# flyingpi.net
KiCad netlist of a schematic drawn in Altium Designer
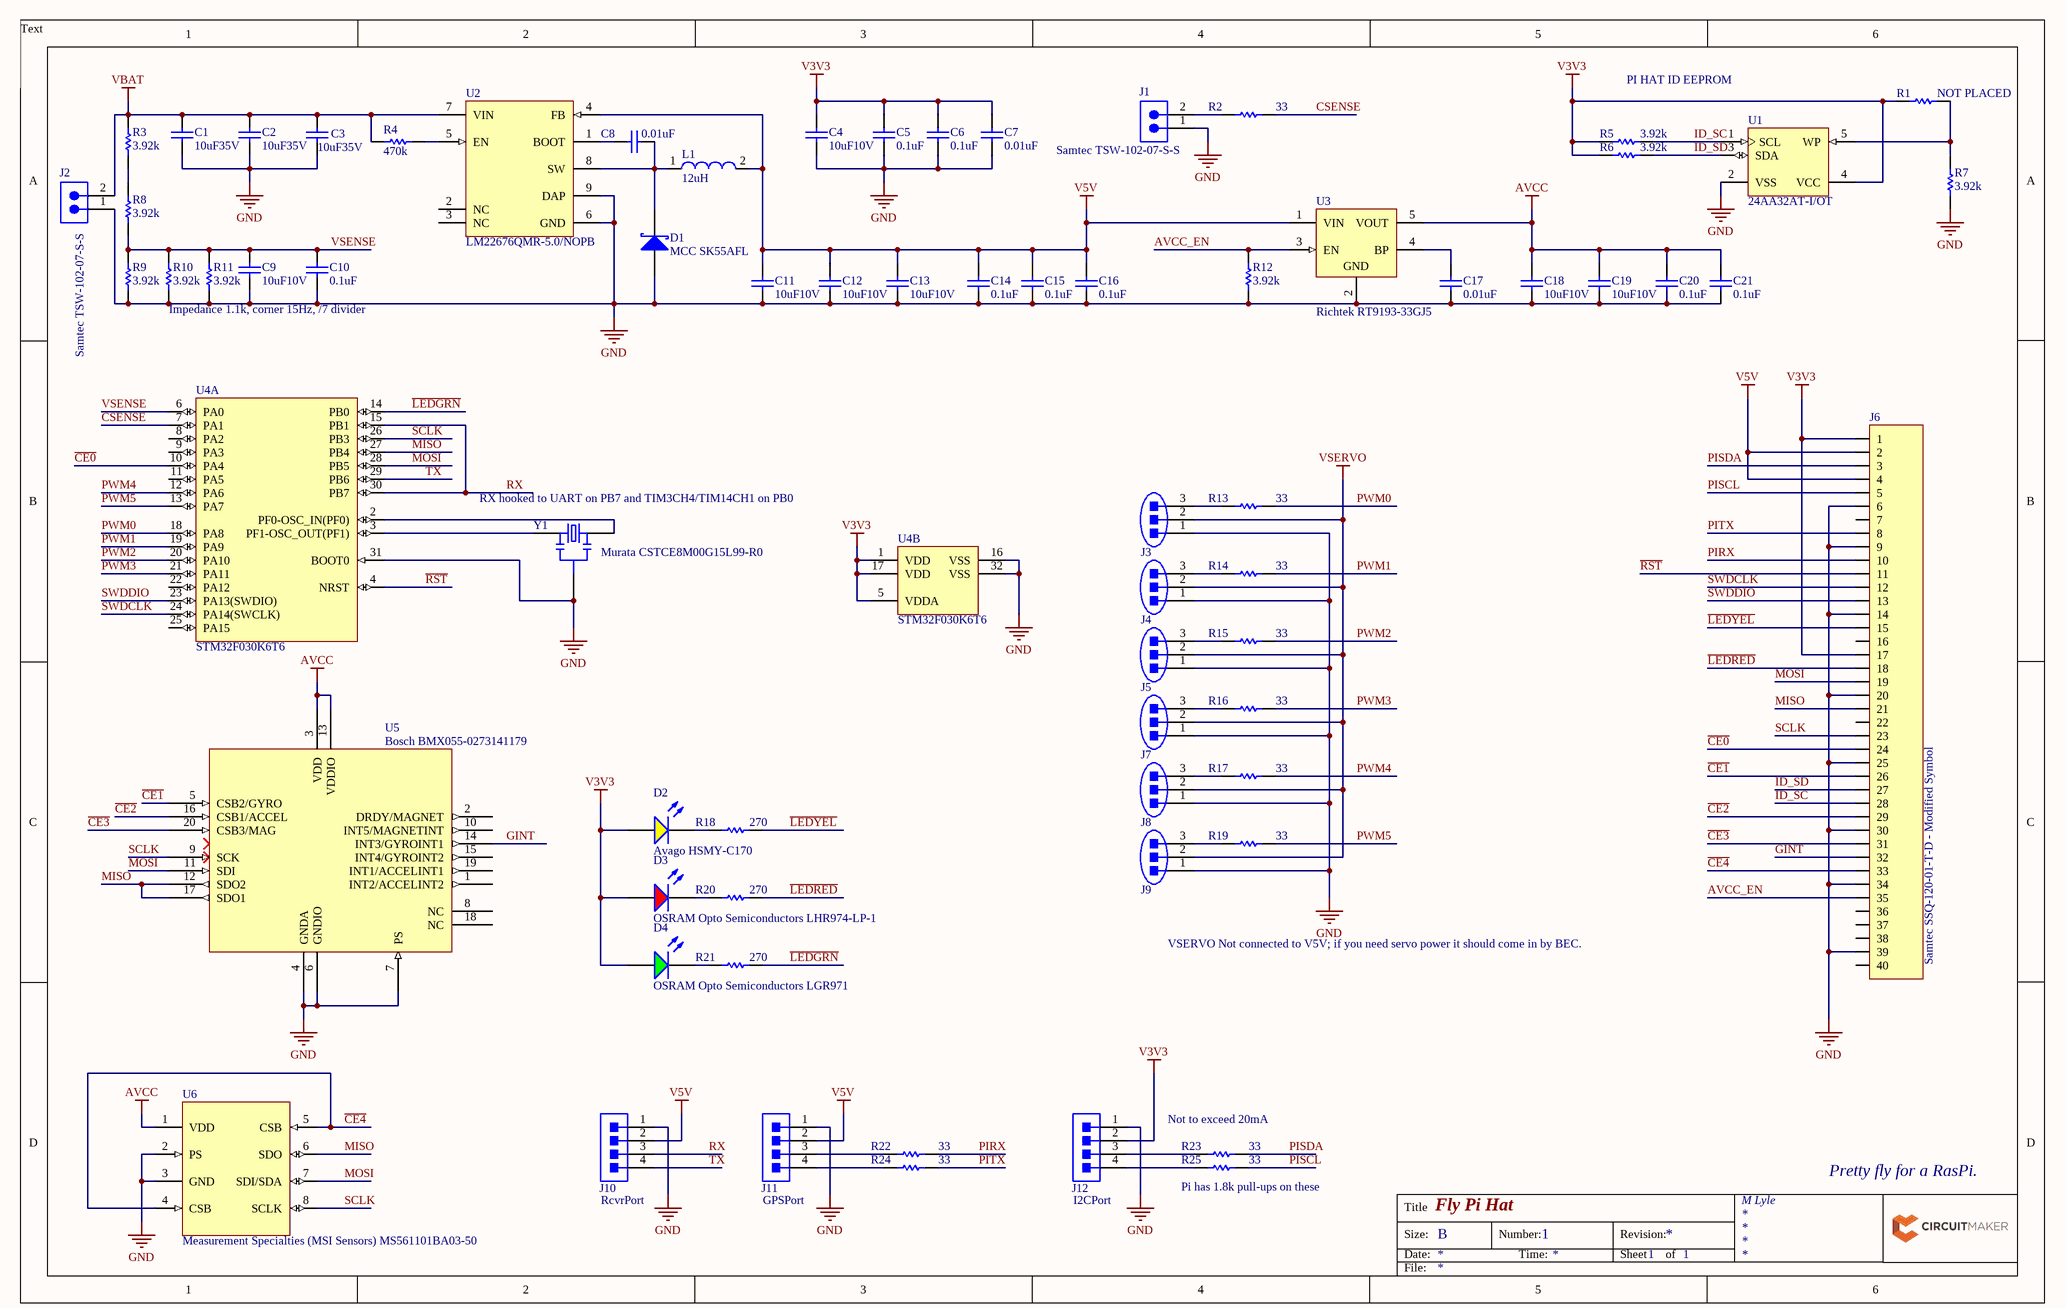
[diagram p0: flyingpi.SchDoc]

(export (version "E")
  (design (tool "Eeschema 10.0.6"))
  (components
    (comp (ref "C1")
      (value "10uF35V")
      (footprint "PCB-4097432-1")
      (description "CAP CER 10UF 35V 10% X5R 0805")
      (libsource (lib "Octopart library") (part "SYM-8857307-2"))
    )
    (comp (ref "C2")
      (value "10uF35V")
      (footprint "PCB-4097432-1")
      (description "CAP CER 10UF 35V 10% X5R 0805")
      (libsource (lib "Octopart library") (part "SYM-8857307-2"))
    )
    (comp (ref "C3")
      (value "10uF35V")
      (footprint "PCB-4097432-1")
      (description "CAP CER 10UF 35V 10% X5R 0805")
      (libsource (lib "Octopart library") (part "SYM-8857307-2"))
    )
    (comp (ref "C4")
      (value "10uF10V")
      (footprint "PCB-11286000-1")
      (description "Cap Ceramic 10uF 10V X5R 10% SMD 0603 85C Paper T/R")
      (libsource (lib "Octopart library") (part "SYM-11286000-1"))
    )
    (comp (ref "C5")
      (value "0.1uF")
      (footprint "CAPC1608X90X35LL10T15")
      (description "CAP CER 0.1UF 16V 10% X7R 0603")
      (libsource (lib "CommunityVault") (part "CAP-2"))
    )
    (comp (ref "C6")
      (value "0.1uF")
      (footprint "CAPC1608X90X35LL10T15")
      (description "CAP CER 0.1UF 16V 10% X7R 0603")
      (libsource (lib "CommunityVault") (part "CAP-2"))
    )
    (comp (ref "C7")
      (value "0.01uF")
      (footprint "0603C")
      (description "0603 10nF 50V ±10 % Tolerance X7R SMT Multilayer Ceramic Capacitor")
      (fields (field (name "MANUFACTURER PART NUMBER") "GRM188R71H103KA01D"))
      (libsource (lib "Octopart library") (part "CAP-NP-2"))
    )
    (comp (ref "C8")
      (value "0.01uF")
      (footprint "0603C")
      (description "0603 10nF 50V ±10 % Tolerance X7R SMT Multilayer Ceramic Capacitor")
      (fields (field (name "MANUFACTURER PART NUMBER") "GRM188R71H103KA01D"))
      (libsource (lib "Octopart library") (part "CAP-NP-2"))
    )
    (comp (ref "C9")
      (value "10uF10V")
      (footprint "PCB-11286000-1")
      (description "Cap Ceramic 10uF 10V X5R 10% SMD 0603 85C Paper T/R")
      (libsource (lib "Octopart library") (part "SYM-11286000-1"))
    )
    (comp (ref "C10")
      (value "0.1uF")
      (footprint "CAPC1608X90X35LL10T15")
      (description "CAP CER 0.1UF 16V 10% X7R 0603")
      (libsource (lib "CommunityVault") (part "CAP-2"))
    )
    (comp (ref "C11")
      (value "10uF10V")
      (footprint "PCB-11286000-1")
      (description "Cap Ceramic 10uF 10V X5R 10% SMD 0603 85C Paper T/R")
      (libsource (lib "Octopart library") (part "SYM-11286000-1"))
    )
    (comp (ref "C12")
      (value "10uF10V")
      (footprint "PCB-11286000-1")
      (description "Cap Ceramic 10uF 10V X5R 10% SMD 0603 85C Paper T/R")
      (libsource (lib "Octopart library") (part "SYM-11286000-1"))
    )
    (comp (ref "C13")
      (value "10uF10V")
      (footprint "PCB-11286000-1")
      (description "Cap Ceramic 10uF 10V X5R 10% SMD 0603 85C Paper T/R")
      (libsource (lib "Octopart library") (part "SYM-11286000-1"))
    )
    (comp (ref "C14")
      (value "0.1uF")
      (footprint "CAPC1608X90X35LL10T15")
      (description "CAP CER 0.1UF 16V 10% X7R 0603")
      (libsource (lib "CommunityVault") (part "CAP-2"))
    )
    (comp (ref "C15")
      (value "0.1uF")
      (footprint "CAPC1608X90X35LL10T15")
      (description "CAP CER 0.1UF 16V 10% X7R 0603")
      (libsource (lib "CommunityVault") (part "CAP-2"))
    )
    (comp (ref "C16")
      (value "0.1uF")
      (footprint "CAPC1608X90X35LL10T15")
      (description "CAP CER 0.1UF 16V 10% X7R 0603")
      (libsource (lib "CommunityVault") (part "CAP-2"))
    )
    (comp (ref "C17")
      (value "0.01uF")
      (footprint "0603C")
      (description "0603 10nF 50V ±10 % Tolerance X7R SMT Multilayer Ceramic Capacitor")
      (fields (field (name "MANUFACTURER PART NUMBER") "GRM188R71H103KA01D"))
      (libsource (lib "Octopart library") (part "CAP-NP-2"))
    )
    (comp (ref "C18")
      (value "10uF10V")
      (footprint "PCB-11286000-1")
      (description "Cap Ceramic 10uF 10V X5R 10% SMD 0603 85C Paper T/R")
      (libsource (lib "Octopart library") (part "SYM-11286000-1"))
    )
    (comp (ref "C19")
      (value "10uF10V")
      (footprint "PCB-11286000-1")
      (description "Cap Ceramic 10uF 10V X5R 10% SMD 0603 85C Paper T/R")
      (libsource (lib "Octopart library") (part "SYM-11286000-1"))
    )
    (comp (ref "C20")
      (value "0.1uF")
      (footprint "CAPC1608X90X35LL10T15")
      (description "CAP CER 0.1UF 16V 10% X7R 0603")
      (libsource (lib "CommunityVault") (part "CAP-2"))
    )
    (comp (ref "C21")
      (value "0.1uF")
      (footprint "CAPC1608X90X35LL10T15")
      (description "CAP CER 0.1UF 16V 10% X7R 0603")
      (libsource (lib "CommunityVault") (part "CAP-2"))
    )
    (comp (ref "D1")
      (value "MCC SK55AFL")
      (footprint "SODFL500X120-2N")
      (description "Diode Schottky 50v 5a Do221ac")
      (fields (field (name "MANUFACTURER PART NUMBER") "SK55AFL-TP"))
      (libsource (lib "Octopart library") (part "SYM-87164cce30a458d1-1"))
    )
    (comp (ref "D2")
      (value "Avago HSMY-C170")
      (footprint "SMD_LED0805")
      (description "LED 589NM YELLOW DIFF 0805 SMD")
      (libsource (lib "Octopart library") (part "LED-YELLOW-C1A2-2"))
    )
    (comp (ref "D3")
      (value "OSRAM Opto Semiconductors LHR974-LP-1")
      (footprint "LED0805")
      (description "LED CHIPLED 645NM RED DIFF 0805")
      (libsource (lib "CommunityVault") (part "LED_RED-C1A2-2"))
    )
    (comp (ref "D4")
      (value "OSRAM Opto Semiconductors LGR971")
      (footprint "LED0805")
      (description "Osram Opto CHIPLED 0805 Series 0805 Green LED, 160")
      (libsource (lib "CommunityVault") (part "LED_GREEN_C1A2-2"))
    )
    (comp (ref "J1")
      (value "Samtec TSW-102-07-S-S")
      (footprint "HDR102")
      (description "CONN HEADER 2POS .100\" SGL GOLD")
      (libsource (lib "CommunityVault") (part "Header_2x1"))
    )
    (comp (ref "J2")
      (value "Samtec TSW-102-07-S-S")
      (footprint "HDR102")
      (description "CONN HEADER 2POS .100\" SGL GOLD")
      (libsource (lib "CommunityVault") (part "Header_2x1"))
    )
    (comp (ref "J3")
      (value "TE Connectivity (Tyco Electronics) 5-146280-3")
      (footprint "HDR1x3_100mil")
      (description "CONN HEADR BRKWAY .100 3POS STR")
      (libsource (lib "CommunityVault") (part "SYM-663837-1"))
    )
    (comp (ref "J4")
      (value "TE Connectivity (Tyco Electronics) 5-146280-3")
      (footprint "HDR1x3_100mil")
      (description "CONN HEADR BRKWAY .100 3POS STR")
      (libsource (lib "CommunityVault") (part "SYM-663837-1"))
    )
    (comp (ref "J5")
      (value "TE Connectivity (Tyco Electronics) 5-146280-3")
      (footprint "HDR1x3_100mil")
      (description "CONN HEADR BRKWAY .100 3POS STR")
      (libsource (lib "CommunityVault") (part "SYM-663837-1"))
    )
    (comp (ref "J6")
      (value "Samtec SSQ-120-01-T-D - Modified Symbol")
      (footprint "PCB-677180-1")
      (description "CONN RCPT .100\" 40POS DUAL TIN")
      (libsource (lib "CommunityVault") (part "SYM-677180-1"))
    )
    (comp (ref "J7")
      (value "TE Connectivity (Tyco Electronics) 5-146280-3")
      (footprint "HDR1x3_100mil")
      (description "CONN HEADR BRKWAY .100 3POS STR")
      (libsource (lib "CommunityVault") (part "SYM-663837-1"))
    )
    (comp (ref "J8")
      (value "TE Connectivity (Tyco Electronics) 5-146280-3")
      (footprint "HDR1x3_100mil")
      (description "CONN HEADR BRKWAY .100 3POS STR")
      (libsource (lib "CommunityVault") (part "SYM-663837-1"))
    )
    (comp (ref "J9")
      (value "TE Connectivity (Tyco Electronics) 5-146280-3")
      (footprint "HDR1x3_100mil")
      (description "CONN HEADR BRKWAY .100 3POS STR")
      (libsource (lib "CommunityVault") (part "SYM-663837-1"))
    )
    (comp (ref "J10")
      (value "TE Connectivity (Tyco Electronics) 3-644456-4")
      (footprint "PCB-640283-1")
      (description "CONN HEADER VERT 4POS .100 TIN")
      (libsource (lib "CommunityVault") (part "SYM-640283-1"))
    )
    (comp (ref "J11")
      (value "TE Connectivity (Tyco Electronics) 3-644456-4")
      (footprint "PCB-640283-1")
      (description "CONN HEADER VERT 4POS .100 TIN")
      (libsource (lib "CommunityVault") (part "SYM-640283-1"))
    )
    (comp (ref "J12")
      (value "TE Connectivity (Tyco Electronics) 3-644456-4")
      (footprint "PCB-640283-1")
      (description "CONN HEADER VERT 4POS .100 TIN")
      (libsource (lib "CommunityVault") (part "SYM-640283-1"))
    )
    (comp (ref "L1")
      (value "12uH")
      (footprint "WE-PD-L")
      (description "SMD-Shielded Power Inductor WE-PD, L = 12.0 µH")
      (libsource (lib "Octopart library") (part "PAS-IND-INDUCTOR-2"))
    )
    (comp (ref "R1")
      (value "NOT PLACED")
      (footprint "RESC1609X50X30LL10T20")
      (description "RES SMD 3.92K OHM 1% 1/10W 0603")
      (libsource (lib "CommunityVault") (part "RES-2"))
    )
    (comp (ref "R2")
      (value "33")
      (footprint "RESC1609X50X30LL10T20")
      (description "RES SMD 33 OHM 1% 1/10W 0603")
      (libsource (lib "CommunityVault") (part "RES-2"))
    )
    (comp (ref "R3")
      (value "3.92k")
      (footprint "RESC1609X50X30LL10T20")
      (description "RES SMD 3.92K OHM 1% 1/10W 0603")
      (libsource (lib "CommunityVault") (part "RES-2"))
    )
    (comp (ref "R4")
      (value "470k")
      (footprint "RESC1608X55X30LL15T15")
      (description "Res Thick Film 0603 470K Ohm 1% 0.1W(1/10W) ±100ppm/C Molded SMD Automotive Punched T/R")
      (libsource (lib "Octopart library") (part "RES-2"))
    )
    (comp (ref "R5")
      (value "3.92k")
      (footprint "RESC1609X50X30LL10T20")
      (description "RES SMD 3.92K OHM 1% 1/10W 0603")
      (libsource (lib "CommunityVault") (part "RES-2"))
    )
    (comp (ref "R6")
      (value "3.92k")
      (footprint "RESC1609X50X30LL10T20")
      (description "RES SMD 3.92K OHM 1% 1/10W 0603")
      (libsource (lib "CommunityVault") (part "RES-2"))
    )
    (comp (ref "R7")
      (value "3.92k")
      (footprint "RESC1609X50X30LL10T20")
      (description "RES SMD 3.92K OHM 1% 1/10W 0603")
      (libsource (lib "CommunityVault") (part "RES-2"))
    )
    (comp (ref "R8")
      (value "3.92k")
      (footprint "RESC1609X50X30LL10T20")
      (description "RES SMD 3.92K OHM 1% 1/10W 0603")
      (libsource (lib "CommunityVault") (part "RES-2"))
    )
    (comp (ref "R9")
      (value "3.92k")
      (footprint "RESC1609X50X30LL10T20")
      (description "RES SMD 3.92K OHM 1% 1/10W 0603")
      (libsource (lib "CommunityVault") (part "RES-2"))
    )
    (comp (ref "R10")
      (value "3.92k")
      (footprint "RESC1609X50X30LL10T20")
      (description "RES SMD 3.92K OHM 1% 1/10W 0603")
      (libsource (lib "CommunityVault") (part "RES-2"))
    )
    (comp (ref "R11")
      (value "3.92k")
      (footprint "RESC1609X50X30LL10T20")
      (description "RES SMD 3.92K OHM 1% 1/10W 0603")
      (libsource (lib "CommunityVault") (part "RES-2"))
    )
    (comp (ref "R12")
      (value "3.92k")
      (footprint "RESC1609X50X30LL10T20")
      (description "RES SMD 3.92K OHM 1% 1/10W 0603")
      (libsource (lib "CommunityVault") (part "RES-2"))
    )
    (comp (ref "R13")
      (value "33")
      (footprint "RESC1609X50X30LL10T20")
      (description "RES SMD 33 OHM 1% 1/10W 0603")
      (libsource (lib "CommunityVault") (part "RES-2"))
    )
    (comp (ref "R14")
      (value "33")
      (footprint "RESC1609X50X30LL10T20")
      (description "RES SMD 33 OHM 1% 1/10W 0603")
      (libsource (lib "CommunityVault") (part "RES-2"))
    )
    (comp (ref "R15")
      (value "33")
      (footprint "RESC1609X50X30LL10T20")
      (description "RES SMD 33 OHM 1% 1/10W 0603")
      (libsource (lib "CommunityVault") (part "RES-2"))
    )
    (comp (ref "R16")
      (value "33")
      (footprint "RESC1609X50X30LL10T20")
      (description "RES SMD 33 OHM 1% 1/10W 0603")
      (libsource (lib "CommunityVault") (part "RES-2"))
    )
    (comp (ref "R17")
      (value "33")
      (footprint "RESC1609X50X30LL10T20")
      (description "RES SMD 33 OHM 1% 1/10W 0603")
      (libsource (lib "CommunityVault") (part "RES-2"))
    )
    (comp (ref "R18")
      (value "270")
      (footprint "RESC1609X50X30LL10T20")
      (description "RES SMD 270 OHM 5% 1/10W 0603")
      (libsource (lib "CommunityVault") (part "RES-2"))
    )
    (comp (ref "R19")
      (value "33")
      (footprint "RESC1609X50X30LL10T20")
      (description "RES SMD 33 OHM 1% 1/10W 0603")
      (libsource (lib "CommunityVault") (part "RES-2"))
    )
    (comp (ref "R20")
      (value "270")
      (footprint "RESC1609X50X30LL10T20")
      (description "RES SMD 270 OHM 5% 1/10W 0603")
      (libsource (lib "CommunityVault") (part "RES-2"))
    )
    (comp (ref "R21")
      (value "270")
      (footprint "RESC1609X50X30LL10T20")
      (description "RES SMD 270 OHM 5% 1/10W 0603")
      (libsource (lib "CommunityVault") (part "RES-2"))
    )
    (comp (ref "R22")
      (value "33")
      (footprint "RESC1609X50X30LL10T20")
      (description "RES SMD 33 OHM 1% 1/10W 0603")
      (libsource (lib "CommunityVault") (part "RES-2"))
    )
    (comp (ref "R23")
      (value "33")
      (footprint "RESC1609X50X30LL10T20")
      (description "RES SMD 33 OHM 1% 1/10W 0603")
      (libsource (lib "CommunityVault") (part "RES-2"))
    )
    (comp (ref "R24")
      (value "33")
      (footprint "RESC1609X50X30LL10T20")
      (description "RES SMD 33 OHM 1% 1/10W 0603")
      (libsource (lib "CommunityVault") (part "RES-2"))
    )
    (comp (ref "R25")
      (value "33")
      (footprint "RESC1609X50X30LL10T20")
      (description "RES SMD 33 OHM 1% 1/10W 0603")
      (libsource (lib "CommunityVault") (part "RES-2"))
    )
    (comp (ref "U1")
      (value "24AA32AT-I/OT")
      (footprint "SOT-23-OT5_L")
      (description "32Kbit, 400kHz, 1.7V, I2C Serial EEPROM, 5-Pin SOT-23, Industrial Temperature, Tape and Reel")
      (libsource (lib "CommunityVault") (part "MEM-SEEPROM-24AA16-OT-5"))
    )
    (comp (ref "U2")
      (value "LM22676QMR-5.0/NOPB")
      (footprint "MRA08B_M")
      (libsource (lib "Octopart library") (part "PM-REG-LM22676MR"))
    )
    (comp (ref "U3")
      (value "Richtek RT9193-33GJ5")
      (footprint "PCB-1508243-1")
      (description "IC REG LDO 3.3V 0.3A TSOT23-5")
      (libsource (lib "Octopart library") (part "SYM-1508243-1"))
    )
    (comp (ref "U4")
      (value "STM32F030K6T6")
      (footprint "STM-LQFP32_N")
      (libsource (lib "Octopart library") (part "MC-ARM-STM32F030-SQ32"))
    )
    (comp (ref "U5")
      (value "Bosch BMX055-0273141179")
      (footprint "LGA20")
      (description "BMX055 Sensor 9-Axis ±2/±4/±8/±16 g 3 V Small Versatile Sensor Module - LGA-20")
      (fields (field (name "MANUFACTURER PART NUMBER") "BMX055-0273141179"))
      (libsource (lib "Octopart library") (part "SYM-ae7c646ba71f71bb-1"))
    )
    (comp (ref "U6")
      (value "Measurement Specialties (MSI Sensors) MS561101BA03-50")
      (footprint "PCB-13001525-1")
      (description "MEASUREMENT SPECIALTIES   MS561101BA03-50   SENSOR, BAROMETRIC, 0.01-1.2BAR, QFN-8")
      (libsource (lib "Octopart library") (part "SYM-13001525-1"))
    )
    (comp (ref "Y1")
      (value "Murata CSTCE8M00G15L99-R0")
      (footprint "X3-SMD-3.6X1.3X0.8MM")
      (description "Ceramic Resonator 8MHz Ø¢±0.1% (Tol) Ø¢±0.08% (Stability) 33pF 40Ohm 3-Pin CSMD T/R")
      (fields (field (name "MANUFACTURER PART NUMBER") "CSTCE8M00G15L99-R0"))
      (libsource (lib "Octopart library") (part "XTAL-RESONATOR-3"))
    )
  )
  (nets
    (net (code "1") (name "/AVCC_EN") (class "Default")
      (node (ref "J6") (pin "35") (pinfunction "35_35") (pintype "passive"))
      (node (ref "R12") (pin "1") (pinfunction "1_1") (pintype "passive"))
      (node (ref "U3") (pin "3") (pinfunction "EN_3") (pintype "input"))
    )
    (net (code "2") (name "/CSENSE") (class "Default")
      (node (ref "R2") (pin "1") (pinfunction "1_1") (pintype "passive"))
      (node (ref "U4") (pin "7") (pinfunction "PA1_7") (pintype "bidirectional"))
    )
    (net (code "3") (name "/GINT") (class "Default")
      (node (ref "J6") (pin "32") (pinfunction "32_32") (pintype "passive"))
      (node (ref "U5") (pin "14") (pinfunction "INT3/GYROINT1_14") (pintype "output"))
    )
    (net (code "4") (name "/ID_SC") (class "Default")
      (node (ref "J6") (pin "28") (pinfunction "28_28") (pintype "passive"))
      (node (ref "R5") (pin "1") (pinfunction "1_1") (pintype "passive"))
      (node (ref "U1") (pin "1") (pinfunction "SCL_1") (pintype "input"))
    )
    (net (code "5") (name "/ID_SD") (class "Default")
      (node (ref "J6") (pin "27") (pinfunction "27_27") (pintype "passive"))
      (node (ref "R6") (pin "1") (pinfunction "1_1") (pintype "passive"))
      (node (ref "U1") (pin "3") (pinfunction "SDA_3") (pintype "bidirectional"))
    )
    (net (code "6") (name "/MISO") (class "Default")
      (node (ref "J6") (pin "21") (pinfunction "21_21") (pintype "passive"))
      (node (ref "U4") (pin "27") (pinfunction "PB4_27") (pintype "bidirectional"))
      (node (ref "U5") (pin "12") (pinfunction "SDO2_12") (pintype "output"))
      (node (ref "U5") (pin "17") (pinfunction "SDO1_17") (pintype "output"))
      (node (ref "U6") (pin "6") (pinfunction "SDO_6") (pintype "bidirectional"))
    )
    (net (code "7") (name "/MOSI") (class "Default")
      (node (ref "J6") (pin "19") (pinfunction "19_19") (pintype "passive"))
      (node (ref "U4") (pin "28") (pinfunction "PB5_28") (pintype "bidirectional"))
      (node (ref "U5") (pin "11") (pinfunction "SDI_11") (pintype "input"))
      (node (ref "U6") (pin "7") (pinfunction "SDI/SDA_7") (pintype "bidirectional"))
    )
    (net (code "8") (name "/PIRX") (class "Default")
      (node (ref "J6") (pin "10") (pinfunction "10_10") (pintype "passive"))
      (node (ref "R22") (pin "1") (pinfunction "1_1") (pintype "passive"))
    )
    (net (code "9") (name "/PISCL") (class "Default")
      (node (ref "J6") (pin "5") (pinfunction "5_5") (pintype "passive"))
      (node (ref "R25") (pin "1") (pinfunction "1_1") (pintype "passive"))
    )
    (net (code "10") (name "/PISDA") (class "Default")
      (node (ref "J6") (pin "3") (pinfunction "3_3") (pintype "passive"))
      (node (ref "R23") (pin "1") (pinfunction "1_1") (pintype "passive"))
    )
    (net (code "11") (name "/PITX") (class "Default")
      (node (ref "J6") (pin "8") (pinfunction "8_8") (pintype "passive"))
      (node (ref "R24") (pin "1") (pinfunction "1_1") (pintype "passive"))
    )
    (net (code "12") (name "/PWM0") (class "Default")
      (node (ref "R13") (pin "1") (pinfunction "1_1") (pintype "passive"))
      (node (ref "U4") (pin "18") (pinfunction "PA8_18") (pintype "bidirectional"))
    )
    (net (code "13") (name "/PWM1") (class "Default")
      (node (ref "R14") (pin "1") (pinfunction "1_1") (pintype "passive"))
      (node (ref "U4") (pin "19") (pinfunction "PA9_19") (pintype "bidirectional"))
    )
    (net (code "14") (name "/PWM2") (class "Default")
      (node (ref "R15") (pin "1") (pinfunction "1_1") (pintype "passive"))
      (node (ref "U4") (pin "20") (pinfunction "PA10_20") (pintype "bidirectional"))
    )
    (net (code "15") (name "/PWM3") (class "Default")
      (node (ref "R16") (pin "1") (pinfunction "1_1") (pintype "passive"))
      (node (ref "U4") (pin "21") (pinfunction "PA11_21") (pintype "bidirectional"))
    )
    (net (code "16") (name "/PWM4") (class "Default")
      (node (ref "R17") (pin "1") (pinfunction "1_1") (pintype "passive"))
      (node (ref "U4") (pin "12") (pinfunction "PA6_12") (pintype "bidirectional"))
    )
    (net (code "17") (name "/PWM5") (class "Default")
      (node (ref "R19") (pin "1") (pinfunction "1_1") (pintype "passive"))
      (node (ref "U4") (pin "13") (pinfunction "PA7_13") (pintype "bidirectional"))
    )
    (net (code "18") (name "/RX") (class "Default")
      (node (ref "J10") (pin "3") (pinfunction "3_3") (pintype "passive"))
      (node (ref "U4") (pin "15") (pinfunction "PB1_15") (pintype "bidirectional"))
      (node (ref "U4") (pin "30") (pinfunction "PB7_30") (pintype "bidirectional"))
    )
    (net (code "19") (name "/SCLK") (class "Default")
      (node (ref "J6") (pin "23") (pinfunction "23_23") (pintype "passive"))
      (node (ref "U4") (pin "26") (pinfunction "PB3_26") (pintype "bidirectional"))
      (node (ref "U5") (pin "9") (pinfunction "SCK_9") (pintype "input"))
      (node (ref "U6") (pin "8") (pinfunction "SCLK_8") (pintype "bidirectional"))
    )
    (net (code "20") (name "/SWDCLK") (class "Default")
      (node (ref "J6") (pin "12") (pinfunction "12_12") (pintype "passive"))
      (node (ref "U4") (pin "24") (pinfunction "PA14(SWCLK)_24") (pintype "bidirectional"))
    )
    (net (code "21") (name "/SWDDIO") (class "Default")
      (node (ref "J6") (pin "13") (pinfunction "13_13") (pintype "passive"))
      (node (ref "U4") (pin "23") (pinfunction "PA13(SWDIO)_23") (pintype "bidirectional"))
    )
    (net (code "22") (name "/TX") (class "Default")
      (node (ref "J10") (pin "4") (pinfunction "4_4") (pintype "passive"))
      (node (ref "U4") (pin "29") (pinfunction "PB6_29") (pintype "bidirectional"))
    )
    (net (code "23") (name "/VSENSE") (class "Default")
      (node (ref "C10") (pin "2") (pinfunction "2_2") (pintype "passive"))
      (node (ref "C9") (pin "2") (pinfunction "2_2") (pintype "passive"))
      (node (ref "R10") (pin "2") (pinfunction "2_2") (pintype "passive"))
      (node (ref "R11") (pin "2") (pinfunction "2_2") (pintype "passive"))
      (node (ref "R8") (pin "1") (pinfunction "1_1") (pintype "passive"))
      (node (ref "R9") (pin "2") (pinfunction "2_2") (pintype "passive"))
      (node (ref "U4") (pin "6") (pinfunction "PA0_6") (pintype "bidirectional"))
    )
    (net (code "24") (name "/~{CE0}") (class "Default")
      (node (ref "J6") (pin "24") (pinfunction "24_24") (pintype "passive"))
      (node (ref "U4") (pin "10") (pinfunction "PA4_10") (pintype "bidirectional"))
    )
    (net (code "25") (name "/~{CE1}") (class "Default")
      (node (ref "J6") (pin "26") (pinfunction "26_26") (pintype "passive"))
      (node (ref "U5") (pin "5") (pinfunction "CSB2/GYRO_5") (pintype "input"))
    )
    (net (code "26") (name "/~{CE2}") (class "Default")
      (node (ref "J6") (pin "29") (pinfunction "29_29") (pintype "passive"))
      (node (ref "U5") (pin "16") (pinfunction "CSB1/ACCEL_16") (pintype "input"))
    )
    (net (code "27") (name "/~{CE3}") (class "Default")
      (node (ref "J6") (pin "31") (pinfunction "31_31") (pintype "passive"))
      (node (ref "U5") (pin "20") (pinfunction "CSB3/MAG_20") (pintype "input"))
    )
    (net (code "28") (name "/~{CE4}") (class "Default")
      (node (ref "J6") (pin "33") (pinfunction "33_33") (pintype "passive"))
      (node (ref "U6") (pin "4") (pinfunction "CSB_4") (pintype "input"))
      (node (ref "U6") (pin "5") (pinfunction "CSB_5") (pintype "input"))
    )
    (net (code "29") (name "/~{LEDGRN}") (class "Default")
      (node (ref "R21") (pin "1") (pinfunction "1_1") (pintype "passive"))
      (node (ref "U4") (pin "14") (pinfunction "PB0_14") (pintype "bidirectional"))
    )
    (net (code "30") (name "/~{LEDRED}") (class "Default")
      (node (ref "J6") (pin "18") (pinfunction "18_18") (pintype "passive"))
      (node (ref "R20") (pin "1") (pinfunction "1_1") (pintype "passive"))
    )
    (net (code "31") (name "/~{LEDYEL}") (class "Default")
      (node (ref "J6") (pin "15") (pinfunction "15_15") (pintype "passive"))
      (node (ref "R18") (pin "1") (pinfunction "1_1") (pintype "passive"))
    )
    (net (code "32") (name "/~{RST}") (class "Default")
      (node (ref "J6") (pin "11") (pinfunction "11_11") (pintype "passive"))
      (node (ref "U4") (pin "4") (pinfunction "NRST_4") (pintype "bidirectional"))
    )
    (net (code "33") (name "AVCC") (class "Default")
      (node (ref "C18") (pin "2") (pinfunction "2_2") (pintype "passive"))
      (node (ref "C19") (pin "2") (pinfunction "2_2") (pintype "passive"))
      (node (ref "C20") (pin "2") (pinfunction "2_2") (pintype "passive"))
      (node (ref "C21") (pin "2") (pinfunction "2_2") (pintype "passive"))
      (node (ref "U3") (pin "5") (pinfunction "VOUT_5") (pintype "power_in"))
      (node (ref "U5") (pin "13") (pinfunction "VDDIO_13") (pintype "power_in"))
      (node (ref "U5") (pin "3") (pinfunction "VDD_3") (pintype "power_in"))
      (node (ref "U6") (pin "1") (pinfunction "VDD_1") (pintype "power_in"))
    )
    (net (code "34") (name "GND") (class "Default")
      (node (ref "C1") (pin "1") (pinfunction "1_1") (pintype "passive"))
      (node (ref "C10") (pin "1") (pinfunction "1_1") (pintype "passive"))
      (node (ref "C11") (pin "1") (pinfunction "1_1") (pintype "passive"))
      (node (ref "C12") (pin "1") (pinfunction "1_1") (pintype "passive"))
      (node (ref "C13") (pin "1") (pinfunction "1_1") (pintype "passive"))
      (node (ref "C14") (pin "1") (pinfunction "1_1") (pintype "passive"))
      (node (ref "C15") (pin "1") (pinfunction "1_1") (pintype "passive"))
      (node (ref "C16") (pin "1") (pinfunction "1_1") (pintype "passive"))
      (node (ref "C17") (pin "1") (pinfunction "1_1") (pintype "passive"))
      (node (ref "C18") (pin "1") (pinfunction "1_1") (pintype "passive"))
      (node (ref "C19") (pin "1") (pinfunction "1_1") (pintype "passive"))
      (node (ref "C2") (pin "1") (pinfunction "1_1") (pintype "passive"))
      (node (ref "C20") (pin "1") (pinfunction "1_1") (pintype "passive"))
      (node (ref "C21") (pin "1") (pinfunction "1_1") (pintype "passive"))
      (node (ref "C3") (pin "1") (pinfunction "1_1") (pintype "passive"))
      (node (ref "C4") (pin "1") (pinfunction "1_1") (pintype "passive"))
      (node (ref "C5") (pin "1") (pinfunction "1_1") (pintype "passive"))
      (node (ref "C6") (pin "1") (pinfunction "1_1") (pintype "passive"))
      (node (ref "C7") (pin "1") (pinfunction "1_1") (pintype "passive"))
      (node (ref "C9") (pin "1") (pinfunction "1_1") (pintype "passive"))
      (node (ref "D1") (pin "1") (pinfunction "A_1") (pintype "passive"))
      (node (ref "J1") (pin "1") (pinfunction "1_1") (pintype "passive"))
      (node (ref "J10") (pin "1") (pinfunction "1_1") (pintype "passive"))
      (node (ref "J11") (pin "1") (pinfunction "1_1") (pintype "passive"))
      (node (ref "J12") (pin "1") (pinfunction "1_1") (pintype "passive"))
      (node (ref "J2") (pin "1") (pinfunction "1_1") (pintype "passive"))
      (node (ref "J3") (pin "1") (pinfunction "1_1") (pintype "passive"))
      (node (ref "J4") (pin "1") (pinfunction "1_1") (pintype "passive"))
      (node (ref "J5") (pin "1") (pinfunction "1_1") (pintype "passive"))
      (node (ref "J6") (pin "14") (pinfunction "14_14") (pintype "passive"))
      (node (ref "J6") (pin "20") (pinfunction "20_20") (pintype "passive"))
      (node (ref "J6") (pin "25") (pinfunction "25_25") (pintype "passive"))
      (node (ref "J6") (pin "30") (pinfunction "30_30") (pintype "passive"))
      (node (ref "J6") (pin "34") (pinfunction "34_34") (pintype "passive"))
      (node (ref "J6") (pin "39") (pinfunction "39_39") (pintype "passive"))
      (node (ref "J6") (pin "6") (pinfunction "6_6") (pintype "passive"))
      (node (ref "J6") (pin "9") (pinfunction "9_9") (pintype "passive"))
      (node (ref "J7") (pin "1") (pinfunction "1_1") (pintype "passive"))
      (node (ref "J8") (pin "1") (pinfunction "1_1") (pintype "passive"))
      (node (ref "J9") (pin "1") (pinfunction "1_1") (pintype "passive"))
      (node (ref "R10") (pin "1") (pinfunction "1_1") (pintype "passive"))
      (node (ref "R11") (pin "1") (pinfunction "1_1") (pintype "passive"))
      (node (ref "R12") (pin "2") (pinfunction "2_2") (pintype "passive"))
      (node (ref "R7") (pin "2") (pinfunction "2_2") (pintype "passive"))
      (node (ref "R9") (pin "1") (pinfunction "1_1") (pintype "passive"))
      (node (ref "U1") (pin "2") (pinfunction "VSS_2") (pintype "power_in"))
      (node (ref "U2") (pin "6") (pinfunction "GND_6") (pintype "power_in"))
      (node (ref "U2") (pin "9") (pinfunction "DAP_9") (pintype "power_in"))
      (node (ref "U3") (pin "2") (pinfunction "GND_2") (pintype "power_in"))
      (node (ref "U4") (pin "16") (pinfunction "VSS_16") (pintype "power_in"))
      (node (ref "U4") (pin "31") (pinfunction "BOOT0_31") (pintype "input"))
      (node (ref "U4") (pin "32") (pinfunction "VSS_32") (pintype "power_in"))
      (node (ref "U5") (pin "4") (pinfunction "GNDA_4") (pintype "power_in"))
      (node (ref "U5") (pin "6") (pinfunction "GNDIO_6") (pintype "power_in"))
      (node (ref "U5") (pin "7") (pinfunction "PS_7") (pintype "input"))
      (node (ref "U6") (pin "2") (pinfunction "PS_2") (pintype "input"))
      (node (ref "U6") (pin "3") (pinfunction "GND_3") (pintype "power_in"))
      (node (ref "Y1") (pin "2") (pinfunction "2_2") (pintype "passive"))
    )
    (net (code "35") (name "Net-(D1-K)") (class "Default")
      (node (ref "C8") (pin "2") (pinfunction "2_2") (pintype "passive"))
      (node (ref "D1") (pin "2") (pinfunction "K_2") (pintype "passive"))
      (node (ref "L1") (pin "1") (pinfunction "1_1") (pintype "passive"))
      (node (ref "U2") (pin "8") (pinfunction "SW_8") (pintype "power_in"))
    )
    (net (code "36") (name "Net-(D2-C)") (class "Default")
      (node (ref "D2") (pin "1") (pinfunction "C_1") (pintype "passive"))
      (node (ref "R18") (pin "2") (pinfunction "2_2") (pintype "passive"))
    )
    (net (code "37") (name "Net-(D3-C)") (class "Default")
      (node (ref "D3") (pin "1") (pinfunction "C_1") (pintype "passive"))
      (node (ref "R20") (pin "2") (pinfunction "2_2") (pintype "passive"))
    )
    (net (code "38") (name "Net-(D4-C)") (class "Default")
      (node (ref "D4") (pin "1") (pinfunction "C_1") (pintype "passive"))
      (node (ref "R21") (pin "2") (pinfunction "2_2") (pintype "passive"))
    )
    (net (code "39") (name "Net-(J1-Pad2)") (class "Default")
      (node (ref "J1") (pin "2") (pinfunction "2_2") (pintype "passive"))
      (node (ref "R2") (pin "2") (pinfunction "2_2") (pintype "passive"))
    )
    (net (code "40") (name "Net-(J3-Pad3)") (class "Default")
      (node (ref "J3") (pin "3") (pinfunction "3_3") (pintype "passive"))
      (node (ref "R13") (pin "2") (pinfunction "2_2") (pintype "passive"))
    )
    (net (code "41") (name "Net-(J4-Pad3)") (class "Default")
      (node (ref "J4") (pin "3") (pinfunction "3_3") (pintype "passive"))
      (node (ref "R14") (pin "2") (pinfunction "2_2") (pintype "passive"))
    )
    (net (code "42") (name "Net-(J5-Pad3)") (class "Default")
      (node (ref "J5") (pin "3") (pinfunction "3_3") (pintype "passive"))
      (node (ref "R15") (pin "2") (pinfunction "2_2") (pintype "passive"))
    )
    (net (code "43") (name "Net-(J7-Pad3)") (class "Default")
      (node (ref "J7") (pin "3") (pinfunction "3_3") (pintype "passive"))
      (node (ref "R16") (pin "2") (pinfunction "2_2") (pintype "passive"))
    )
    (net (code "44") (name "Net-(J8-Pad3)") (class "Default")
      (node (ref "J8") (pin "3") (pinfunction "3_3") (pintype "passive"))
      (node (ref "R17") (pin "2") (pinfunction "2_2") (pintype "passive"))
    )
    (net (code "45") (name "Net-(J9-Pad3)") (class "Default")
      (node (ref "J9") (pin "3") (pinfunction "3_3") (pintype "passive"))
      (node (ref "R19") (pin "2") (pinfunction "2_2") (pintype "passive"))
    )
    (net (code "46") (name "Net-(J11-Pad3)") (class "Default")
      (node (ref "J11") (pin "3") (pinfunction "3_3") (pintype "passive"))
      (node (ref "R22") (pin "2") (pinfunction "2_2") (pintype "passive"))
    )
    (net (code "47") (name "Net-(J11-Pad4)") (class "Default")
      (node (ref "J11") (pin "4") (pinfunction "4_4") (pintype "passive"))
      (node (ref "R24") (pin "2") (pinfunction "2_2") (pintype "passive"))
    )
    (net (code "48") (name "Net-(J12-Pad3)") (class "Default")
      (node (ref "J12") (pin "3") (pinfunction "3_3") (pintype "passive"))
      (node (ref "R23") (pin "2") (pinfunction "2_2") (pintype "passive"))
    )
    (net (code "49") (name "Net-(J12-Pad4)") (class "Default")
      (node (ref "J12") (pin "4") (pinfunction "4_4") (pintype "passive"))
      (node (ref "R25") (pin "2") (pinfunction "2_2") (pintype "passive"))
    )
    (net (code "50") (name "Net-(R3-Pad1)") (class "Default")
      (node (ref "R3") (pin "1") (pinfunction "1_1") (pintype "passive"))
      (node (ref "R8") (pin "2") (pinfunction "2_2") (pintype "passive"))
    )
    (net (code "51") (name "Net-(U1-WP)") (class "Default")
      (node (ref "R1") (pin "2") (pinfunction "2_2") (pintype "passive"))
      (node (ref "R7") (pin "1") (pinfunction "1_1") (pintype "passive"))
      (node (ref "U1") (pin "5") (pinfunction "WP_5") (pintype "input"))
    )
    (net (code "52") (name "Net-(U2-BOOT)") (class "Default")
      (node (ref "C8") (pin "1") (pinfunction "1_1") (pintype "passive"))
      (node (ref "U2") (pin "1") (pinfunction "BOOT_1") (pintype "passive"))
    )
    (net (code "53") (name "Net-(U2-EN)") (class "Default")
      (node (ref "R4") (pin "2") (pinfunction "2_2") (pintype "passive"))
      (node (ref "U2") (pin "5") (pinfunction "EN_5") (pintype "input"))
    )
    (net (code "54") (name "Net-(U3-BP)") (class "Default")
      (node (ref "C17") (pin "2") (pinfunction "2_2") (pintype "passive"))
      (node (ref "U3") (pin "4") (pinfunction "BP_4") (pintype "passive"))
    )
    (net (code "55") (name "Net-(U4A-PF0-OSC_IN(PF0))") (class "Default")
      (node (ref "U4") (pin "2") (pinfunction "PF0-OSC_IN(PF0)_2") (pintype "bidirectional"))
      (node (ref "Y1") (pin "3") (pinfunction "3_3") (pintype "passive"))
    )
    (net (code "56") (name "Net-(U4A-PF1-OSC_OUT(PF1))") (class "Default")
      (node (ref "U4") (pin "3") (pinfunction "PF1-OSC_OUT(PF1)_3") (pintype "bidirectional"))
      (node (ref "Y1") (pin "1") (pinfunction "1_1") (pintype "passive"))
    )
    (net (code "57") (name "V3V3") (class "Default")
      (node (ref "C4") (pin "2") (pinfunction "2_2") (pintype "passive"))
      (node (ref "C5") (pin "2") (pinfunction "2_2") (pintype "passive"))
      (node (ref "C6") (pin "2") (pinfunction "2_2") (pintype "passive"))
      (node (ref "C7") (pin "2") (pinfunction "2_2") (pintype "passive"))
      (node (ref "D2") (pin "2") (pinfunction "A_2") (pintype "passive"))
      (node (ref "D3") (pin "2") (pinfunction "A_2") (pintype "passive"))
      (node (ref "D4") (pin "2") (pinfunction "A_2") (pintype "passive"))
      (node (ref "J12") (pin "2") (pinfunction "2_2") (pintype "passive"))
      (node (ref "J6") (pin "1") (pinfunction "1_1") (pintype "passive"))
      (node (ref "J6") (pin "17") (pinfunction "17_17") (pintype "passive"))
      (node (ref "R1") (pin "1") (pinfunction "1_1") (pintype "passive"))
      (node (ref "R5") (pin "2") (pinfunction "2_2") (pintype "passive"))
      (node (ref "R6") (pin "2") (pinfunction "2_2") (pintype "passive"))
      (node (ref "U1") (pin "4") (pinfunction "VCC_4") (pintype "power_in"))
      (node (ref "U4") (pin "1") (pinfunction "VDD_1") (pintype "power_in"))
      (node (ref "U4") (pin "17") (pinfunction "VDD_17") (pintype "power_in"))
      (node (ref "U4") (pin "5") (pinfunction "VDDA_5") (pintype "power_in"))
    )
    (net (code "58") (name "V5V") (class "Default")
      (node (ref "C11") (pin "2") (pinfunction "2_2") (pintype "passive"))
      (node (ref "C12") (pin "2") (pinfunction "2_2") (pintype "passive"))
      (node (ref "C13") (pin "2") (pinfunction "2_2") (pintype "passive"))
      (node (ref "C14") (pin "2") (pinfunction "2_2") (pintype "passive"))
      (node (ref "C15") (pin "2") (pinfunction "2_2") (pintype "passive"))
      (node (ref "C16") (pin "2") (pinfunction "2_2") (pintype "passive"))
      (node (ref "J10") (pin "2") (pinfunction "2_2") (pintype "passive"))
      (node (ref "J11") (pin "2") (pinfunction "2_2") (pintype "passive"))
      (node (ref "J6") (pin "2") (pinfunction "2_2") (pintype "passive"))
      (node (ref "J6") (pin "4") (pinfunction "4_4") (pintype "passive"))
      (node (ref "L1") (pin "2") (pinfunction "2_2") (pintype "passive"))
      (node (ref "U2") (pin "4") (pinfunction "FB_4") (pintype "input"))
      (node (ref "U3") (pin "1") (pinfunction "VIN_1") (pintype "power_in"))
    )
    (net (code "59") (name "VBAT") (class "Default")
      (node (ref "C1") (pin "2") (pinfunction "2_2") (pintype "passive"))
      (node (ref "C2") (pin "2") (pinfunction "2_2") (pintype "passive"))
      (node (ref "C3") (pin "2") (pinfunction "2_2") (pintype "passive"))
      (node (ref "J2") (pin "2") (pinfunction "2_2") (pintype "passive"))
      (node (ref "R3") (pin "2") (pinfunction "2_2") (pintype "passive"))
      (node (ref "R4") (pin "1") (pinfunction "1_1") (pintype "passive"))
      (node (ref "U2") (pin "7") (pinfunction "VIN_7") (pintype "power_in"))
    )
    (net (code "60") (name "VSERVO") (class "Default")
      (node (ref "J3") (pin "2") (pinfunction "2_2") (pintype "passive"))
      (node (ref "J4") (pin "2") (pinfunction "2_2") (pintype "passive"))
      (node (ref "J5") (pin "2") (pinfunction "2_2") (pintype "passive"))
      (node (ref "J7") (pin "2") (pinfunction "2_2") (pintype "passive"))
      (node (ref "J8") (pin "2") (pinfunction "2_2") (pintype "passive"))
      (node (ref "J9") (pin "2") (pinfunction "2_2") (pintype "passive"))
    )
    (net (code "61") (name "unconnected-(J6-Pad7)") (class "Default")
      (node (ref "J6") (pin "7") (pinfunction "7_7") (pintype "passive"))
    )
    (net (code "62") (name "unconnected-(J6-Pad16)") (class "Default")
      (node (ref "J6") (pin "16") (pinfunction "16_16") (pintype "passive"))
    )
    (net (code "63") (name "unconnected-(J6-Pad22)") (class "Default")
      (node (ref "J6") (pin "22") (pinfunction "22_22") (pintype "passive"))
    )
    (net (code "64") (name "unconnected-(J6-Pad36)") (class "Default")
      (node (ref "J6") (pin "36") (pinfunction "36_36") (pintype "passive"))
    )
    (net (code "65") (name "unconnected-(J6-Pad37)") (class "Default")
      (node (ref "J6") (pin "37") (pinfunction "37_37") (pintype "passive"))
    )
    (net (code "66") (name "unconnected-(J6-Pad38)") (class "Default")
      (node (ref "J6") (pin "38") (pinfunction "38_38") (pintype "passive"))
    )
    (net (code "67") (name "unconnected-(J6-Pad40)") (class "Default")
      (node (ref "J6") (pin "40") (pinfunction "40_40") (pintype "passive"))
    )
    (net (code "68") (name "unconnected-(U2-NC-Pad2)") (class "Default")
      (node (ref "U2") (pin "2") (pinfunction "NC_2") (pintype "passive"))
    )
    (net (code "69") (name "unconnected-(U2-NC-Pad3)") (class "Default")
      (node (ref "U2") (pin "3") (pinfunction "NC_3") (pintype "passive"))
    )
    (net (code "70") (name "unconnected-(U4A-PA2-Pad8)") (class "Default")
      (node (ref "U4") (pin "8") (pinfunction "PA2_8") (pintype "bidirectional"))
    )
    (net (code "71") (name "unconnected-(U4A-PA3-Pad9)") (class "Default")
      (node (ref "U4") (pin "9") (pinfunction "PA3_9") (pintype "bidirectional"))
    )
    (net (code "72") (name "unconnected-(U4A-PA5-Pad11)") (class "Default")
      (node (ref "U4") (pin "11") (pinfunction "PA5_11") (pintype "bidirectional"))
    )
    (net (code "73") (name "unconnected-(U4A-PA12-Pad22)") (class "Default")
      (node (ref "U4") (pin "22") (pinfunction "PA12_22") (pintype "bidirectional"))
    )
    (net (code "74") (name "unconnected-(U4A-PA15-Pad25)") (class "Default")
      (node (ref "U4") (pin "25") (pinfunction "PA15_25") (pintype "bidirectional"))
    )
    (net (code "75") (name "unconnected-(U5-DRDY{slash}MAGNET-Pad2)") (class "Default")
      (node (ref "U5") (pin "2") (pinfunction "DRDY/MAGNET_2") (pintype "output"))
    )
    (net (code "76") (name "unconnected-(U5-INT1{slash}ACCELINT1-Pad19)") (class "Default")
      (node (ref "U5") (pin "19") (pinfunction "INT1/ACCELINT1_19") (pintype "output"))
    )
    (net (code "77") (name "unconnected-(U5-INT2{slash}ACCELINT2-Pad1)") (class "Default")
      (node (ref "U5") (pin "1") (pinfunction "INT2/ACCELINT2_1") (pintype "output"))
    )
    (net (code "78") (name "unconnected-(U5-INT4{slash}GYROINT2-Pad15)") (class "Default")
      (node (ref "U5") (pin "15") (pinfunction "INT4/GYROINT2_15") (pintype "output"))
    )
    (net (code "79") (name "unconnected-(U5-INT5{slash}MAGNETINT-Pad10)") (class "Default")
      (node (ref "U5") (pin "10") (pinfunction "INT5/MAGNETINT_10") (pintype "output"))
    )
    (net (code "80") (name "unconnected-(U5-NC-Pad8)") (class "Default")
      (node (ref "U5") (pin "8") (pinfunction "NC_8") (pintype "passive"))
    )
    (net (code "81") (name "unconnected-(U5-NC-Pad18)") (class "Default")
      (node (ref "U5") (pin "18") (pinfunction "NC_18") (pintype "passive"))
    )
  )
)
